# Lab_10_Starter.net
KiCad netlist of a schematic drawn in EAGLE
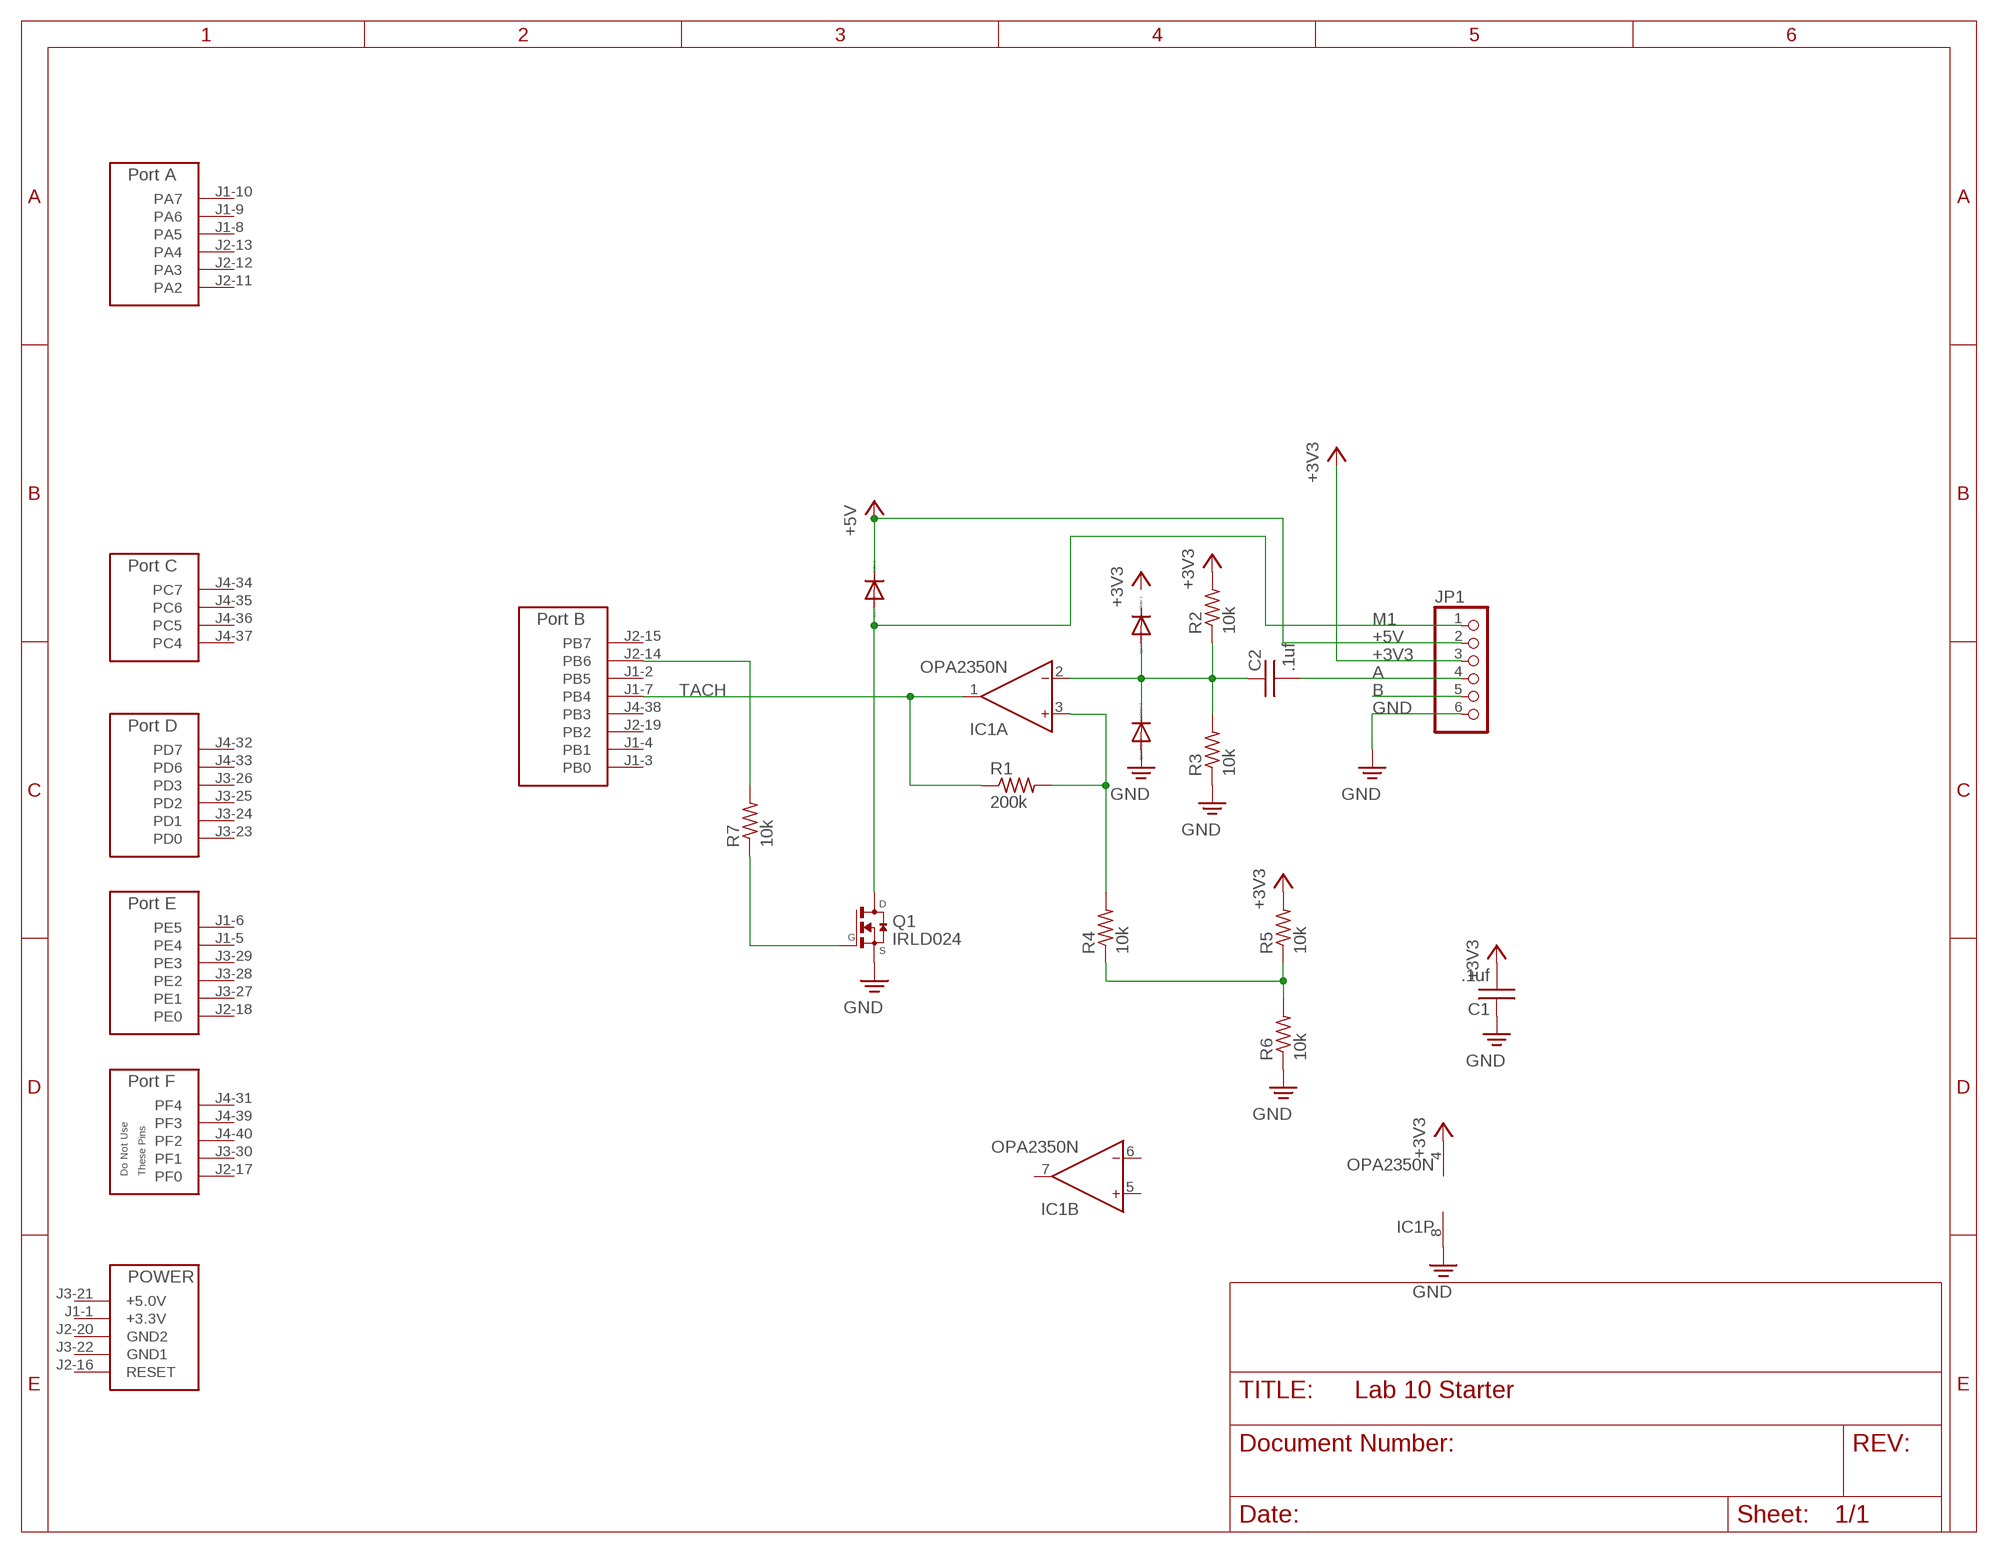
[diagram p0: schematic, sheet 1]

(export (version "E")
  (design (tool "Eeschema 10.0.6"))
  (components
    (comp (ref "C1")
      (value ".1uf")
      (footprint "eagle-import:CAP100MIL")
      (libsource (lib "eagle-import") (part "CAPACITOR025-024X044"))
    )
    (comp (ref "C2")
      (value ".1uf")
      (footprint "eagle-import:CAP100MIL")
      (libsource (lib "eagle-import") (part "CAPACITOR025-024X044"))
    )
    (comp (ref "D1")
      (value "1N914DO35-7")
      (footprint "eagle-import:DO35-7")
      (libsource (lib "eagle-import") (part "1N914DO35-7"))
    )
    (comp (ref "D2")
      (value "1N914DO35-7")
      (footprint "eagle-import:DO35-7")
      (libsource (lib "eagle-import") (part "1N914DO35-7"))
    )
    (comp (ref "D3")
      (value "1N914DO35-7")
      (footprint "eagle-import:DO35-7")
      (libsource (lib "eagle-import") (part "1N914DO35-7"))
    )
    (comp (ref "IC1")
      (value "OPA2350N")
      (footprint "eagle-import:DIL08")
      (libsource (lib "eagle-import") (part "OPA2350N"))
    )
    (comp (ref "JP1")
      (value "PINHD-1X6")
      (footprint "eagle-import:1X06")
      (libsource (lib "eagle-import") (part "PINHD-1X6"))
    )
    (comp (ref "Q1")
      (value "IRLD024")
      (footprint "eagle-import:IRLD024")
      (libsource (lib "eagle-import") (part "IRLD024"))
    )
    (comp (ref "R1")
      (value "200k")
      (footprint "eagle-import:RES200MIL")
      (libsource (lib "eagle-import") (part "RESISTOR0204/5"))
    )
    (comp (ref "R2")
      (value "10k")
      (footprint "eagle-import:RES200MIL")
      (libsource (lib "eagle-import") (part "RESISTOR0204/5"))
    )
    (comp (ref "R3")
      (value "10k")
      (footprint "eagle-import:RES200MIL")
      (libsource (lib "eagle-import") (part "RESISTOR0204/5"))
    )
    (comp (ref "R4")
      (value "10k")
      (footprint "eagle-import:RES200MIL")
      (libsource (lib "eagle-import") (part "RESISTOR0204/5"))
    )
    (comp (ref "R5")
      (value "10k")
      (footprint "eagle-import:RES200MIL")
      (libsource (lib "eagle-import") (part "RESISTOR0204/5"))
    )
    (comp (ref "R6")
      (value "10k")
      (footprint "eagle-import:RES200MIL")
      (libsource (lib "eagle-import") (part "RESISTOR0204/5"))
    )
    (comp (ref "R7")
      (value "10k")
      (footprint "eagle-import:RES200MIL")
      (libsource (lib "eagle-import") (part "RESISTOR0204/5"))
    )
    (comp (ref "U$1")
      (value "TM4C_BP")
      (footprint "eagle-import:TM4C_BOOSTER_PACK")
      (libsource (lib "eagle-import") (part "TM4C_BP"))
    )
  )
  (nets
    (net (code "1") (name "+3V3") (class "Default")
      (node (ref "C1") (pin "2") (pinfunction "2_2") (pintype "passive"))
      (node (ref "IC1") (pin "4") (pinfunction "V-_4") (pintype "power_in"))
      (node (ref "JP1") (pin "3") (pinfunction "3_3") (pintype "passive"))
      (node (ref "R2") (pin "2") (pinfunction "2_2") (pintype "passive"))
      (node (ref "R5") (pin "2") (pinfunction "2_2") (pintype "passive"))
    )
    (net (code "2") (name "+5V") (class "Default")
      (node (ref "D3") (pin "C") (pinfunction "C_C") (pintype "passive"))
      (node (ref "JP1") (pin "2") (pinfunction "2_2") (pintype "passive"))
    )
    (net (code "3") (name "/A") (class "Default")
      (node (ref "C2") (pin "2") (pinfunction "2_2") (pintype "passive"))
      (node (ref "JP1") (pin "4") (pinfunction "4_4") (pintype "passive"))
    )
    (net (code "4") (name "/B") (class "Default")
      (node (ref "JP1") (pin "5") (pinfunction "5_5") (pintype "passive"))
    )
    (net (code "5") (name "/M1") (class "Default")
      (node (ref "D3") (pin "A") (pinfunction "A_A") (pintype "passive"))
      (node (ref "JP1") (pin "1") (pinfunction "1_1") (pintype "passive"))
      (node (ref "Q1") (pin "P$1") (pinfunction "D_P$1") (pintype "passive"))
    )
    (net (code "6") (name "/TACH") (class "Default")
      (node (ref "IC1") (pin "1") (pinfunction "OUT_1") (pintype "output"))
      (node (ref "R1") (pin "1") (pinfunction "1_1") (pintype "passive"))
      (node (ref "U$1") (pin "J1-7") (pinfunction "PB4_J1-7") (pintype "bidirectional"))
    )
    (net (code "7") (name "GND") (class "Default")
      (node (ref "C1") (pin "1") (pinfunction "1_1") (pintype "passive"))
      (node (ref "D2") (pin "A") (pinfunction "A_A") (pintype "passive"))
      (node (ref "IC1") (pin "8") (pinfunction "V+_8") (pintype "power_in"))
      (node (ref "JP1") (pin "6") (pinfunction "6_6") (pintype "passive"))
      (node (ref "Q1") (pin "P$4") (pinfunction "S_P$4") (pintype "passive"))
      (node (ref "R3") (pin "1") (pinfunction "1_1") (pintype "passive"))
      (node (ref "R6") (pin "1") (pinfunction "1_1") (pintype "passive"))
    )
    (net (code "8") (name "Net-(IC1A-IN+)") (class "Default")
      (node (ref "IC1") (pin "3") (pinfunction "IN+_3") (pintype "input"))
      (node (ref "R1") (pin "2") (pinfunction "2_2") (pintype "passive"))
      (node (ref "R4") (pin "2") (pinfunction "2_2") (pintype "passive"))
    )
    (net (code "9") (name "Net-(IC1A-IN-)") (class "Default")
      (node (ref "C2") (pin "1") (pinfunction "1_1") (pintype "passive"))
      (node (ref "D1") (pin "A") (pinfunction "A_A") (pintype "passive"))
      (node (ref "D2") (pin "C") (pinfunction "C_C") (pintype "passive"))
      (node (ref "IC1") (pin "2") (pinfunction "IN-_2") (pintype "input"))
      (node (ref "R2") (pin "1") (pinfunction "1_1") (pintype "passive"))
      (node (ref "R3") (pin "2") (pinfunction "2_2") (pintype "passive"))
    )
    (net (code "10") (name "Net-(Q1-G)") (class "Default")
      (node (ref "Q1") (pin "P$3") (pinfunction "G_P$3") (pintype "passive"))
      (node (ref "R7") (pin "1") (pinfunction "1_1") (pintype "passive"))
    )
    (net (code "11") (name "Net-(R4-Pad1)") (class "Default")
      (node (ref "R4") (pin "1") (pinfunction "1_1") (pintype "passive"))
      (node (ref "R5") (pin "1") (pinfunction "1_1") (pintype "passive"))
      (node (ref "R6") (pin "2") (pinfunction "2_2") (pintype "passive"))
    )
    (net (code "12") (name "Net-(U$1B-PB6)") (class "Default")
      (node (ref "R7") (pin "2") (pinfunction "2_2") (pintype "passive"))
      (node (ref "U$1") (pin "J2-14") (pinfunction "PB6_J2-14") (pintype "bidirectional"))
    )
    (net (code "13") (name "unconnected-(D1-PadC)") (class "Default")
      (node (ref "D1") (pin "C") (pinfunction "C_C") (pintype "passive"))
    )
    (net (code "14") (name "unconnected-(IC1B-IN+-Pad5)") (class "Default")
      (node (ref "IC1") (pin "5") (pinfunction "IN+_5") (pintype "input"))
    )
    (net (code "15") (name "unconnected-(IC1B-IN--Pad6)") (class "Default")
      (node (ref "IC1") (pin "6") (pinfunction "IN-_6") (pintype "input"))
    )
    (net (code "16") (name "unconnected-(IC1B-OUT-Pad7)") (class "Default")
      (node (ref "IC1") (pin "7") (pinfunction "OUT_7") (pintype "output"))
    )
    (net (code "17") (name "unconnected-(U$1A-PA2-PadJ2-11)") (class "Default")
      (node (ref "U$1") (pin "J2-11") (pinfunction "PA2_J2-11") (pintype "bidirectional"))
    )
    (net (code "18") (name "unconnected-(U$1A-PA3-PadJ2-12)") (class "Default")
      (node (ref "U$1") (pin "J2-12") (pinfunction "PA3_J2-12") (pintype "bidirectional"))
    )
    (net (code "19") (name "unconnected-(U$1A-PA4-PadJ2-13)") (class "Default")
      (node (ref "U$1") (pin "J2-13") (pinfunction "PA4_J2-13") (pintype "bidirectional"))
    )
    (net (code "20") (name "unconnected-(U$1A-PA5-PadJ1-8)") (class "Default")
      (node (ref "U$1") (pin "J1-8") (pinfunction "PA5_J1-8") (pintype "bidirectional"))
    )
    (net (code "21") (name "unconnected-(U$1A-PA6-PadJ1-9)") (class "Default")
      (node (ref "U$1") (pin "J1-9") (pinfunction "PA6_J1-9") (pintype "bidirectional"))
    )
    (net (code "22") (name "unconnected-(U$1A-PA7-PadJ1-10)") (class "Default")
      (node (ref "U$1") (pin "J1-10") (pinfunction "PA7_J1-10") (pintype "bidirectional"))
    )
    (net (code "23") (name "unconnected-(U$1B-PB0-PadJ1-3)") (class "Default")
      (node (ref "U$1") (pin "J1-3") (pinfunction "PB0_J1-3") (pintype "bidirectional"))
    )
    (net (code "24") (name "unconnected-(U$1B-PB1-PadJ1-4)") (class "Default")
      (node (ref "U$1") (pin "J1-4") (pinfunction "PB1_J1-4") (pintype "bidirectional"))
    )
    (net (code "25") (name "unconnected-(U$1B-PB2-PadJ2-19)") (class "Default")
      (node (ref "U$1") (pin "J2-19") (pinfunction "PB2_J2-19") (pintype "bidirectional"))
    )
    (net (code "26") (name "unconnected-(U$1B-PB3-PadJ4-38)") (class "Default")
      (node (ref "U$1") (pin "J4-38") (pinfunction "PB3_J4-38") (pintype "bidirectional"))
    )
    (net (code "27") (name "unconnected-(U$1B-PB5-PadJ1-2)") (class "Default")
      (node (ref "U$1") (pin "J1-2") (pinfunction "PB5_J1-2") (pintype "bidirectional"))
    )
    (net (code "28") (name "unconnected-(U$1B-PB7-PadJ2-15)") (class "Default")
      (node (ref "U$1") (pin "J2-15") (pinfunction "PB7_J2-15") (pintype "bidirectional"))
    )
    (net (code "29") (name "unconnected-(U$1C-PC4-PadJ4-37)") (class "Default")
      (node (ref "U$1") (pin "J4-37") (pinfunction "PC4_J4-37") (pintype "bidirectional"))
    )
    (net (code "30") (name "unconnected-(U$1C-PC5-PadJ4-36)") (class "Default")
      (node (ref "U$1") (pin "J4-36") (pinfunction "PC5_J4-36") (pintype "bidirectional"))
    )
    (net (code "31") (name "unconnected-(U$1C-PC6-PadJ4-35)") (class "Default")
      (node (ref "U$1") (pin "J4-35") (pinfunction "PC6_J4-35") (pintype "bidirectional"))
    )
    (net (code "32") (name "unconnected-(U$1C-PC7-PadJ4-34)") (class "Default")
      (node (ref "U$1") (pin "J4-34") (pinfunction "PC7_J4-34") (pintype "bidirectional"))
    )
    (net (code "33") (name "unconnected-(U$1D-PD0-PadJ3-23)") (class "Default")
      (node (ref "U$1") (pin "J3-23") (pinfunction "PD0_J3-23") (pintype "bidirectional"))
    )
    (net (code "34") (name "unconnected-(U$1D-PD1-PadJ3-24)") (class "Default")
      (node (ref "U$1") (pin "J3-24") (pinfunction "PD1_J3-24") (pintype "bidirectional"))
    )
    (net (code "35") (name "unconnected-(U$1D-PD2-PadJ3-25)") (class "Default")
      (node (ref "U$1") (pin "J3-25") (pinfunction "PD2_J3-25") (pintype "bidirectional"))
    )
    (net (code "36") (name "unconnected-(U$1D-PD3-PadJ3-26)") (class "Default")
      (node (ref "U$1") (pin "J3-26") (pinfunction "PD3_J3-26") (pintype "bidirectional"))
    )
    (net (code "37") (name "unconnected-(U$1D-PD6-PadJ4-33)") (class "Default")
      (node (ref "U$1") (pin "J4-33") (pinfunction "PD6_J4-33") (pintype "bidirectional"))
    )
    (net (code "38") (name "unconnected-(U$1D-PD7-PadJ4-32)") (class "Default")
      (node (ref "U$1") (pin "J4-32") (pinfunction "PD7_J4-32") (pintype "bidirectional"))
    )
    (net (code "39") (name "unconnected-(U$1E-PE0-PadJ2-18)") (class "Default")
      (node (ref "U$1") (pin "J2-18") (pinfunction "PE0_J2-18") (pintype "bidirectional"))
    )
    (net (code "40") (name "unconnected-(U$1E-PE1-PadJ3-27)") (class "Default")
      (node (ref "U$1") (pin "J3-27") (pinfunction "PE1_J3-27") (pintype "bidirectional"))
    )
    (net (code "41") (name "unconnected-(U$1E-PE2-PadJ3-28)") (class "Default")
      (node (ref "U$1") (pin "J3-28") (pinfunction "PE2_J3-28") (pintype "bidirectional"))
    )
    (net (code "42") (name "unconnected-(U$1E-PE3-PadJ3-29)") (class "Default")
      (node (ref "U$1") (pin "J3-29") (pinfunction "PE3_J3-29") (pintype "bidirectional"))
    )
    (net (code "43") (name "unconnected-(U$1E-PE4-PadJ1-5)") (class "Default")
      (node (ref "U$1") (pin "J1-5") (pinfunction "PE4_J1-5") (pintype "bidirectional"))
    )
    (net (code "44") (name "unconnected-(U$1E-PE5-PadJ1-6)") (class "Default")
      (node (ref "U$1") (pin "J1-6") (pinfunction "PE5_J1-6") (pintype "bidirectional"))
    )
    (net (code "45") (name "unconnected-(U$1F-PF0-PadJ2-17)") (class "Default")
      (node (ref "U$1") (pin "J2-17") (pinfunction "PF0_J2-17") (pintype "bidirectional"))
    )
    (net (code "46") (name "unconnected-(U$1F-PF1-PadJ3-30)") (class "Default")
      (node (ref "U$1") (pin "J3-30") (pinfunction "PF1_J3-30") (pintype "bidirectional"))
    )
    (net (code "47") (name "unconnected-(U$1F-PF2-PadJ4-40)") (class "Default")
      (node (ref "U$1") (pin "J4-40") (pinfunction "PF2_J4-40") (pintype "bidirectional"))
    )
    (net (code "48") (name "unconnected-(U$1F-PF3-PadJ4-39)") (class "Default")
      (node (ref "U$1") (pin "J4-39") (pinfunction "PF3_J4-39") (pintype "bidirectional"))
    )
    (net (code "49") (name "unconnected-(U$1F-PF4-PadJ4-31)") (class "Default")
      (node (ref "U$1") (pin "J4-31") (pinfunction "PF4_J4-31") (pintype "bidirectional"))
    )
    (net (code "50") (name "unconnected-(U$1G-+3.3V-PadJ1-1)") (class "Default")
      (node (ref "U$1") (pin "J1-1") (pinfunction "+3.3V_J1-1") (pintype "bidirectional"))
    )
    (net (code "51") (name "unconnected-(U$1G-+5.0V-PadJ3-21)") (class "Default")
      (node (ref "U$1") (pin "J3-21") (pinfunction "+5.0V_J3-21") (pintype "bidirectional"))
    )
    (net (code "52") (name "unconnected-(U$1G-GND1-PadJ3-22)") (class "Default")
      (node (ref "U$1") (pin "J3-22") (pinfunction "GND1_J3-22") (pintype "bidirectional"))
    )
    (net (code "53") (name "unconnected-(U$1G-GND2-PadJ2-20)") (class "Default")
      (node (ref "U$1") (pin "J2-20") (pinfunction "GND2_J2-20") (pintype "bidirectional"))
    )
    (net (code "54") (name "unconnected-(U$1G-RESET-PadJ2-16)") (class "Default")
      (node (ref "U$1") (pin "J2-16") (pinfunction "RESET_J2-16") (pintype "bidirectional"))
    )
  )
)
